# COEX_PDB_schematics.net
KiCad netlist of a schematic drawn in Altium Designer
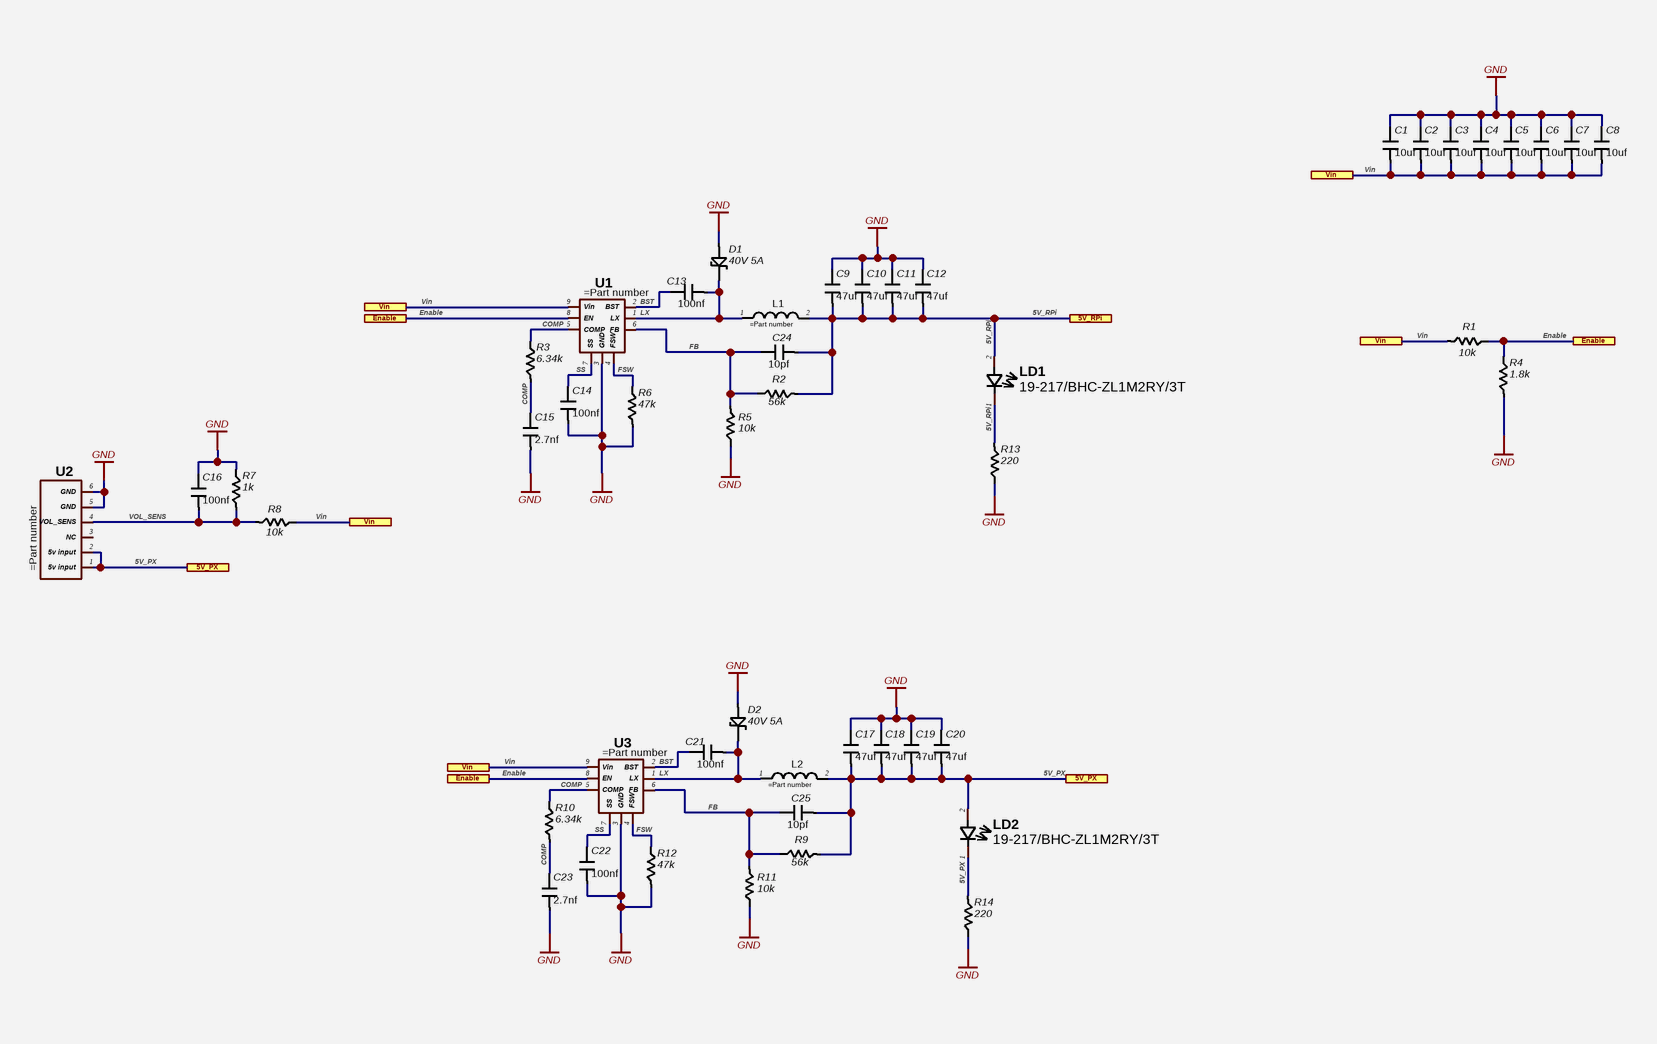
[diagram p0: COEX PDB schematics.SchDoc]

(export (version "E")
  (design (tool "Eeschema 10.0.6"))
  (components
    (comp (ref "C1")
      (value "10uf")
      (footprint "Capasitor 0805")
      (description "10uF ±20% 35V X5R 0805 Multilayer Ceramic Capacitor")
      (fields
        (field (name "PARTNUMBER") "GRM21BR6YA106ME43L")
        (field (name "MANUFACTURER") "Murata Electronics")
      )
      (libsource (lib "Schematic symbols library") (part "Capacitor MLCC"))
    )
    (comp (ref "C2")
      (value "10uf")
      (footprint "Capasitor 0805")
      (description "10uF ±20% 35V X5R 0805 Multilayer Ceramic Capacitor")
      (fields
        (field (name "PARTNUMBER") "GRM21BR6YA106ME43L")
        (field (name "MANUFACTURER") "Murata Electronics")
      )
      (libsource (lib "Schematic symbols library") (part "Capacitor MLCC"))
    )
    (comp (ref "C3")
      (value "10uf")
      (footprint "Capasitor 0805")
      (description "10uF ±20% 35V X5R 0805 Multilayer Ceramic Capacitor")
      (fields
        (field (name "PARTNUMBER") "GRM21BR6YA106ME43L")
        (field (name "MANUFACTURER") "Murata Electronics")
      )
      (libsource (lib "Schematic symbols library") (part "Capacitor MLCC"))
    )
    (comp (ref "C4")
      (value "10uf")
      (footprint "Capasitor 0805")
      (description "10uF ±20% 35V X5R 0805 Multilayer Ceramic Capacitor")
      (fields
        (field (name "PARTNUMBER") "GRM21BR6YA106ME43L")
        (field (name "MANUFACTURER") "Murata Electronics")
      )
      (libsource (lib "") (part "Capacitor MLCC_1"))
    )
    (comp (ref "C5")
      (value "10uf")
      (footprint "Capasitor 0805")
      (description "10uF ±20% 35V X5R 0805 Multilayer Ceramic Capacitor")
      (fields
        (field (name "PARTNUMBER") "GRM21BR6YA106ME43L")
        (field (name "MANUFACTURER") "Murata Electronics")
      )
      (libsource (lib "Schematic symbols library") (part "Capacitor MLCC"))
    )
    (comp (ref "C6")
      (value "10uf")
      (footprint "Capasitor 0805")
      (description "10uF ±20% 35V X5R 0805 Multilayer Ceramic Capacitor")
      (fields
        (field (name "PARTNUMBER") "GRM21BR6YA106ME43L")
        (field (name "MANUFACTURER") "Murata Electronics")
      )
      (libsource (lib "Schematic symbols library") (part "Capacitor MLCC"))
    )
    (comp (ref "C7")
      (value "10uf")
      (footprint "Capasitor 0805")
      (description "10uF ±20% 35V X5R 0805 Multilayer Ceramic Capacitor")
      (fields
        (field (name "PARTNUMBER") "GRM21BR6YA106ME43L")
        (field (name "MANUFACTURER") "Murata Electronics")
      )
      (libsource (lib "Schematic symbols library") (part "Capacitor MLCC"))
    )
    (comp (ref "C8")
      (value "10uf")
      (footprint "Capasitor 0805")
      (description "10uF ±20% 35V X5R 0805 Multilayer Ceramic Capacitor")
      (fields
        (field (name "PARTNUMBER") "GRM21BR6YA106ME43L")
        (field (name "MANUFACTURER") "Murata Electronics")
      )
      (libsource (lib "Schematic symbols library") (part "Capacitor MLCC"))
    )
    (comp (ref "C9")
      (value "47uf")
      (footprint "Capasitor 0805")
      (description "47uF ±20% 6.3V X5R 0805 Multilayer Ceramic Capacitor")
      (fields (field (name "PARTNUMBER") "JMK212BJ476MG-T") (field (name "MANUFACTURER") "Taiyo Yuden"))
      (libsource (lib "Schematic symbols library") (part "Capacitor MLCC"))
    )
    (comp (ref "C10")
      (value "47uf")
      (footprint "Capasitor 0805")
      (description "47uF ±20% 6.3V X5R 0805 Multilayer Ceramic Capacitor")
      (fields (field (name "PARTNUMBER") "JMK212BJ476MG-T") (field (name "MANUFACTURER") "Taiyo Yuden"))
      (libsource (lib "Schematic symbols library") (part "Capacitor MLCC"))
    )
    (comp (ref "C11")
      (value "47uf")
      (footprint "Capasitor 0805")
      (description "47uF ±20% 6.3V X5R 0805 Multilayer Ceramic Capacitor")
      (fields (field (name "PARTNUMBER") "JMK212BJ476MG-T") (field (name "MANUFACTURER") "Taiyo Yuden"))
      (libsource (lib "Schematic symbols library") (part "Capacitor MLCC"))
    )
    (comp (ref "C12")
      (value "47uf")
      (footprint "Capasitor 0805")
      (description "47uF ±20% 6.3V X5R 0805 Multilayer Ceramic Capacitor")
      (fields (field (name "PARTNUMBER") "JMK212BJ476MG-T") (field (name "MANUFACTURER") "Taiyo Yuden"))
      (libsource (lib "Schematic symbols library") (part "Capacitor MLCC"))
    )
    (comp (ref "C13")
      (value "100nf")
      (footprint "Capasitor 0402")
      (description "100nF ±10% 50V X5R 0402 Multilayer Ceramic Capacitor")
      (fields (field (name "PARTNUMBER") "CC0402KRX5R9BB104") (field (name "MANUFACTURER") "YAGEO"))
      (libsource (lib "Schematic symbols library") (part "Capacitor MLCC"))
    )
    (comp (ref "C14")
      (value "100nf")
      (footprint "Capasitor 0402")
      (description "100nF ±10% 50V X5R 0402 Multilayer Ceramic Capacitor")
      (fields (field (name "PARTNUMBER") "CC0402KRX5R9BB104") (field (name "MANUFACTURER") "YAGEO"))
      (libsource (lib "Schematic symbols library") (part "Capacitor MLCC"))
    )
    (comp (ref "C15")
      (value "2.7nf")
      (footprint "Capasitor 0402")
      (description "2.7nF ±10% 50V X7R 0402 Multilayer Ceramic Capacitor")
      (fields (field (name "PARTNUMBER") "CC0402KRX7R9BB272") (field (name "MANUFACTURER") "YAGEO"))
      (libsource (lib "Schematic symbols library") (part "Capacitor MLCC"))
    )
    (comp (ref "C16")
      (value "100nf")
      (footprint "Capasitor 0402")
      (description "100nF ±10% 50V X5R 0402 Multilayer Ceramic Capacitor")
      (fields (field (name "PARTNUMBER") "CC0402KRX5R9BB104") (field (name "MANUFACTURER") "YAGEO"))
      (libsource (lib "Schematic symbols library") (part "Capacitor MLCC"))
    )
    (comp (ref "C17")
      (value "47uf")
      (footprint "Capasitor 0805")
      (description "47uF ±20% 6.3V X5R 0805 Multilayer Ceramic Capacitor")
      (fields (field (name "PARTNUMBER") "JMK212BJ476MG-T") (field (name "MANUFACTURER") "Taiyo Yuden"))
      (libsource (lib "Schematic symbols library") (part "Capacitor MLCC"))
    )
    (comp (ref "C18")
      (value "47uf")
      (footprint "Capasitor 0805")
      (description "47uF ±20% 6.3V X5R 0805 Multilayer Ceramic Capacitor")
      (fields (field (name "PARTNUMBER") "JMK212BJ476MG-T") (field (name "MANUFACTURER") "Taiyo Yuden"))
      (libsource (lib "Schematic symbols library") (part "Capacitor MLCC"))
    )
    (comp (ref "C19")
      (value "47uf")
      (footprint "Capasitor 0805")
      (description "47uF ±20% 6.3V X5R 0805 Multilayer Ceramic Capacitor")
      (fields (field (name "PARTNUMBER") "JMK212BJ476MG-T") (field (name "MANUFACTURER") "Taiyo Yuden"))
      (libsource (lib "Schematic symbols library") (part "Capacitor MLCC"))
    )
    (comp (ref "C20")
      (value "47uf")
      (footprint "Capasitor 0805")
      (description "47uF ±20% 6.3V X5R 0805 Multilayer Ceramic Capacitor")
      (fields (field (name "PARTNUMBER") "JMK212BJ476MG-T") (field (name "MANUFACTURER") "Taiyo Yuden"))
      (libsource (lib "Schematic symbols library") (part "Capacitor MLCC"))
    )
    (comp (ref "C21")
      (value "100nf")
      (footprint "Capasitor 0402")
      (description "100nF ±10% 50V X5R 0402 Multilayer Ceramic Capacitor")
      (fields (field (name "PARTNUMBER") "CC0402KRX5R9BB104") (field (name "MANUFACTURER") "YAGEO"))
      (libsource (lib "Schematic symbols library") (part "Capacitor MLCC"))
    )
    (comp (ref "C22")
      (value "100nf")
      (footprint "Capasitor 0402")
      (description "100nF ±10% 50V X5R 0402 Multilayer Ceramic Capacitor")
      (fields (field (name "PARTNUMBER") "CC0402KRX5R9BB104") (field (name "MANUFACTURER") "YAGEO"))
      (libsource (lib "Schematic symbols library") (part "Capacitor MLCC"))
    )
    (comp (ref "C23")
      (value "2.7nf")
      (footprint "Capasitor 0402")
      (description "2.7nF ±10% 50V X7R 0402 Multilayer Ceramic Capacitor")
      (fields (field (name "PARTNUMBER") "CC0402KRX7R9BB272") (field (name "MANUFACTURER") "YAGEO"))
      (libsource (lib "Schematic symbols library") (part "Capacitor MLCC"))
    )
    (comp (ref "C24")
      (value "10pf")
      (footprint "Capasitor 0402")
      (description "10pF ±5% 50V NP0 0402 Multilayer Ceramic Capacitor")
      (fields (field (name "PARTNUMBER") "CC0402JRNPO9BN100") (field (name "MANUFACTURER") "YAGEO"))
      (libsource (lib "Schematic symbols library") (part "Capacitor MLCC"))
    )
    (comp (ref "C25")
      (value "10pf")
      (footprint "Capasitor 0402")
      (description "10pF ±5% 50V NP0 0402 Multilayer Ceramic Capacitor")
      (fields (field (name "PARTNUMBER") "CC0402JRNPO9BN100") (field (name "MANUFACTURER") "YAGEO"))
      (libsource (lib "Schematic symbols library") (part "Capacitor MLCC"))
    )
    (comp (ref "D1")
      (value "40V 5A")
      (footprint "SMAF")
      (description "40V 5A 450mV @ 5A SMAF Schottky Barrier Diode")
      (fields (field (name "PARTNUMBER") "SL54F") (field (name "MANUFACTURER") "MDD(Microdiode Electronics)"))
      (libsource (lib "Schematic symbols library") (part "Schottky barrier diode"))
    )
    (comp (ref "D2")
      (value "40V 5A")
      (footprint "SMAF")
      (description "40V 5A 450mV @ 5A SMAF Schottky Barrier Diode")
      (fields (field (name "PARTNUMBER") "SL54F") (field (name "MANUFACTURER") "MDD(Microdiode Electronics)"))
      (libsource (lib "Schematic symbols library") (part "Schottky barrier diode"))
    )
    (comp (ref "L1")
      (value "~")
      (footprint "Inductor SMD 7.1x6.6")
      (description "4.7uH ±20% 4.5A 45mΩ SMD,7.1x6.6x2.4mm Power Inductor")
      (fields (field (name "PARTNUMBER") "SLO0624H4R7MTT") (field (name "MANUFACTURER") "Sunltech Tech"))
      (libsource (lib "Schematic symbols library") (part "FB / Inductor"))
    )
    (comp (ref "L2")
      (value "~")
      (footprint "Inductor SMD 7.1x6.6")
      (description "4.7uH ±20% 4.5A 45mΩ SMD,7.1x6.6x2.4mm Power Inductor")
      (fields (field (name "PARTNUMBER") "SLO0624H4R7MTT") (field (name "MANUFACTURER") "Sunltech Tech"))
      (libsource (lib "Schematic symbols library") (part "FB / Inductor"))
    )
    (comp (ref "LD1")
      (value "19-217/BHC-ZL1M2RY/3T")
      (footprint "Led 0603")
      (description "Blue 465~475nm 0603 Light Emitting Diode")
      (fields (field (name "MANUFACTURER") "Everlight Elec"))
      (libsource (lib "Schematic symbols library") (part "LED"))
    )
    (comp (ref "LD2")
      (value "19-217/BHC-ZL1M2RY/3T")
      (footprint "Led 0603")
      (description "Blue 465~475nm 0603 Light Emitting Diode")
      (fields (field (name "MANUFACTURER") "Everlight Elec"))
      (libsource (lib "Schematic symbols library") (part "LED"))
    )
    (comp (ref "R1")
      (value "10k")
      (footprint "Resistor 0402")
      (description "Chip Resistor - Surface Mount 10KOhms ±1% 1/16W 0402")
      (fields (field (name "PARTNUMBER") "RC0402FR-0710KL") (field (name "MANUFACTURER") "YAGEO"))
      (libsource (lib "") (part "Resistor_1"))
    )
    (comp (ref "R2")
      (value "56k")
      (footprint "Resistor 0402")
      (description "Chip Resistor - Surface Mount 56KOhms ±1% 1/16W 0402")
      (fields (field (name "PARTNUMBER") "RC0402FR-0756KL") (field (name "MANUFACTURER") "YAGEO"))
      (libsource (lib "Schematic symbols library") (part "Resistor"))
    )
    (comp (ref "R3")
      (value "6.34k")
      (footprint "Resistor 0402")
      (description "6.34K ±1% 1/16W ±100ppm/°C 0402 Chip Resistor")
      (fields
        (field (name "PARTNUMBER") "0402WGF6341TCE")
        (field (name "MANUFACTURER") "UNI-ROYAL(Uniroyal Elec)")
      )
      (libsource (lib "Schematic symbols library") (part "Resistor"))
    )
    (comp (ref "R4")
      (value "1.8k")
      (footprint "Resistor 0402")
      (description "1.8K ±1% 1/16W ±100ppm/°C 0402 Chip Resistor")
      (fields (field (name "PARTNUMBER") "RTT021801FTH") (field (name "MANUFACTURER") "RALEC"))
      (libsource (lib "Schematic symbols library") (part "Resistor"))
    )
    (comp (ref "R5")
      (value "10k")
      (footprint "Resistor 0402")
      (description "Chip Resistor - Surface Mount 10KOhms ±1% 1/16W 0402")
      (fields (field (name "PARTNUMBER") "RC0402FR-0710KL") (field (name "MANUFACTURER") "YAGEO"))
      (libsource (lib "Schematic symbols library") (part "Resistor"))
    )
    (comp (ref "R6")
      (value "47k")
      (footprint "Resistor 0402")
      (description "47K ±1% 1/16W ±100ppm/°C 0402 Chip Resistor")
      (fields (field (name "PARTNUMBER") "AC0402FR-0747KL") (field (name "MANUFACTURER") "YAGEO"))
      (libsource (lib "Schematic symbols library") (part "Resistor"))
    )
    (comp (ref "R7")
      (value "1k")
      (footprint "Resistor 0402")
      (description "1K ±1% 1/16W ±100ppm/°C 0402 Chip Resistor")
      (fields
        (field (name "PARTNUMBER") "0402WGF1001TCE")
        (field (name "MANUFACTURER") "UNI-ROYAL(Uniroyal Elec)")
      )
      (libsource (lib "Schematic symbols library") (part "Resistor"))
    )
    (comp (ref "R8")
      (value "10k")
      (footprint "Resistor 0402")
      (description "Chip Resistor - Surface Mount 10KOhms ±1% 1/16W 0402")
      (fields (field (name "PARTNUMBER") "RC0402FR-0710KL") (field (name "MANUFACTURER") "YAGEO"))
      (libsource (lib "Schematic symbols library") (part "Resistor"))
    )
    (comp (ref "R9")
      (value "56k")
      (footprint "Resistor 0402")
      (description "Chip Resistor - Surface Mount 56KOhms ±1% 1/16W 0402")
      (fields (field (name "PARTNUMBER") "RC0402FR-0756KL") (field (name "MANUFACTURER") "YAGEO"))
      (libsource (lib "Schematic symbols library") (part "Resistor"))
    )
    (comp (ref "R10")
      (value "6.34k")
      (footprint "Resistor 0402")
      (description "6.34K ±1% 1/16W ±100ppm/°C 0402 Chip Resistor")
      (fields
        (field (name "PARTNUMBER") "0402WGF6341TCE")
        (field (name "MANUFACTURER") "UNI-ROYAL(Uniroyal Elec)")
      )
      (libsource (lib "Schematic symbols library") (part "Resistor"))
    )
    (comp (ref "R11")
      (value "10k")
      (footprint "Resistor 0402")
      (description "Chip Resistor - Surface Mount 10KOhms ±1% 1/16W 0402")
      (fields (field (name "PARTNUMBER") "RC0402FR-0710KL") (field (name "MANUFACTURER") "YAGEO"))
      (libsource (lib "Schematic symbols library") (part "Resistor"))
    )
    (comp (ref "R12")
      (value "47k")
      (footprint "Resistor 0402")
      (description "47K ±1% 1/16W ±100ppm/°C 0402 Chip Resistor")
      (fields (field (name "PARTNUMBER") "AC0402FR-0747KL") (field (name "MANUFACTURER") "YAGEO"))
      (libsource (lib "Schematic symbols library") (part "Resistor"))
    )
    (comp (ref "R13")
      (value "220")
      (footprint "Resistor 0402")
      (description "220 ±1% 1/16W ±200ppm/°C 0402 Chip Resistor")
      (fields
        (field (name "PARTNUMBER") "RC-02W2200FT")
        (field (name "MANUFACTURER") "FH(Guangdong Fenghua Advanced Tech)")
      )
      (libsource (lib "Schematic symbols library") (part "Resistor"))
    )
    (comp (ref "R14")
      (value "220")
      (footprint "Resistor 0402")
      (description "220 ±1% 1/16W ±200ppm/°C 0402 Chip Resistor")
      (fields
        (field (name "PARTNUMBER") "RC-02W2200FT")
        (field (name "MANUFACTURER") "FH(Guangdong Fenghua Advanced Tech)")
      )
      (libsource (lib "Schematic symbols library") (part "Resistor"))
    )
    (comp (ref "U1")
      (value "~")
      (footprint "SOIC-8 (Thermal pad)")
      (description "Step-Down Positive Adjustable 1 4A 200kHz ~ 2MHz SOP-8_EP_150mil DC-DC Converter")
      (fields (field (name "PARTNUMBER") "AOZ1284PI") (field (name "MANUFACTURER") "Alpha & Omega Semicon"))
      (libsource (lib "Schematic symbols library") (part "AOZ1284"))
    )
    (comp (ref "U2")
      (value "~")
      (footprint "JST-GH 6 PIN")
      (description "GH Header Male Pin 0.049\"(1.25mm) 6 SMD Wire To Board / Wire To Wire Connector")
      (fields
        (field (name "PARTNUMBER") "SM06B-GHS-TB(LF)(SN)")
        (field (name "MANUFACTURER") "JST Sales America")
      )
      (libsource (lib "Schematic symbols library") (part "JST-GH 6"))
    )
    (comp (ref "U3")
      (value "~")
      (footprint "SOIC-8 (Thermal pad)")
      (description "Step-Down Positive Adjustable 1 4A 200kHz ~ 2MHz SOP-8_EP_150mil DC-DC Converter")
      (fields (field (name "PARTNUMBER") "AOZ1284PI") (field (name "MANUFACTURER") "Alpha & Omega Semicon"))
      (libsource (lib "Schematic symbols library") (part "AOZ1284"))
    )
  )
  (nets
    (net (code "1") (name "/5V_PX") (class "Default")
      (node (ref "C17") (pin "2") (pinfunction "2_2") (pintype "passive"))
      (node (ref "C18") (pin "2") (pinfunction "2_2") (pintype "passive"))
      (node (ref "C19") (pin "2") (pinfunction "2_2") (pintype "passive"))
      (node (ref "C20") (pin "2") (pinfunction "2_2") (pintype "passive"))
      (node (ref "C25") (pin "2") (pinfunction "2_2") (pintype "passive"))
      (node (ref "L2") (pin "2") (pintype "power_in"))
      (node (ref "LD2") (pin "1") (pintype "power_in"))
      (node (ref "LD2") (pin "2") (pintype "power_in"))
      (node (ref "R14") (pin "2") (pinfunction "2_2") (pintype "passive"))
      (node (ref "R9") (pin "2") (pinfunction "2_2") (pintype "passive"))
      (node (ref "U2") (pin "1") (pinfunction "5v_input_1") (pintype "power_in"))
      (node (ref "U2") (pin "2") (pinfunction "5v_input_2") (pintype "power_in"))
    )
    (net (code "2") (name "/5V_RPi") (class "Default")
      (node (ref "C10") (pin "2") (pinfunction "2_2") (pintype "passive"))
      (node (ref "C11") (pin "2") (pinfunction "2_2") (pintype "passive"))
      (node (ref "C12") (pin "2") (pinfunction "2_2") (pintype "passive"))
      (node (ref "C24") (pin "2") (pinfunction "2_2") (pintype "passive"))
      (node (ref "C9") (pin "2") (pinfunction "2_2") (pintype "passive"))
      (node (ref "L1") (pin "2") (pintype "power_in"))
      (node (ref "LD1") (pin "1") (pintype "power_in"))
      (node (ref "LD1") (pin "2") (pintype "power_in"))
      (node (ref "R13") (pin "2") (pinfunction "2_2") (pintype "passive"))
      (node (ref "R2") (pin "2") (pinfunction "2_2") (pintype "passive"))
    )
    (net (code "3") (name "/BST") (class "Default")
      (node (ref "C13") (pin "1") (pinfunction "1_1") (pintype "passive"))
      (node (ref "C21") (pin "1") (pinfunction "1_1") (pintype "passive"))
      (node (ref "U1") (pin "2") (pinfunction "BST_2") (pintype "power_in"))
      (node (ref "U3") (pin "2") (pinfunction "BST_2") (pintype "power_in"))
    )
    (net (code "4") (name "/COMP") (class "Default")
      (node (ref "C15") (pin "1") (pinfunction "1_1") (pintype "passive"))
      (node (ref "C23") (pin "1") (pinfunction "1_1") (pintype "passive"))
      (node (ref "R10") (pin "1") (pinfunction "1_1") (pintype "passive"))
      (node (ref "R10") (pin "2") (pinfunction "2_2") (pintype "passive"))
      (node (ref "R3") (pin "1") (pinfunction "1_1") (pintype "passive"))
      (node (ref "R3") (pin "2") (pinfunction "2_2") (pintype "passive"))
      (node (ref "U1") (pin "5") (pinfunction "COMP_5") (pintype "power_in"))
      (node (ref "U3") (pin "5") (pinfunction "COMP_5") (pintype "power_in"))
    )
    (net (code "5") (name "/Enable") (class "Default")
      (node (ref "R1") (pin "1") (pinfunction "1_1") (pintype "passive"))
      (node (ref "R4") (pin "1") (pinfunction "1_1") (pintype "passive"))
      (node (ref "U1") (pin "8") (pinfunction "EN_8") (pintype "power_in"))
      (node (ref "U3") (pin "8") (pinfunction "EN_8") (pintype "power_in"))
    )
    (net (code "6") (name "/FB") (class "Default")
      (node (ref "C24") (pin "1") (pinfunction "1_1") (pintype "passive"))
      (node (ref "C25") (pin "1") (pinfunction "1_1") (pintype "passive"))
      (node (ref "R11") (pin "2") (pinfunction "2_2") (pintype "passive"))
      (node (ref "R2") (pin "1") (pinfunction "1_1") (pintype "passive"))
      (node (ref "R5") (pin "2") (pinfunction "2_2") (pintype "passive"))
      (node (ref "R9") (pin "1") (pinfunction "1_1") (pintype "passive"))
      (node (ref "U1") (pin "6") (pinfunction "FB_6") (pintype "power_in"))
      (node (ref "U3") (pin "6") (pinfunction "FB_6") (pintype "power_in"))
    )
    (net (code "7") (name "/FSW") (class "Default")
      (node (ref "R12") (pin "1") (pinfunction "1_1") (pintype "passive"))
      (node (ref "R6") (pin "1") (pinfunction "1_1") (pintype "passive"))
      (node (ref "U1") (pin "4") (pinfunction "FSW_4") (pintype "power_in"))
      (node (ref "U3") (pin "4") (pinfunction "FSW_4") (pintype "power_in"))
    )
    (net (code "8") (name "/LX") (class "Default")
      (node (ref "C13") (pin "2") (pinfunction "2_2") (pintype "passive"))
      (node (ref "C21") (pin "2") (pinfunction "2_2") (pintype "passive"))
      (node (ref "D1") (pin "1") (pinfunction "1_1") (pintype "passive"))
      (node (ref "D2") (pin "1") (pinfunction "1_1") (pintype "passive"))
      (node (ref "L1") (pin "1") (pintype "power_in"))
      (node (ref "L2") (pin "1") (pintype "power_in"))
      (node (ref "U1") (pin "1") (pinfunction "LX_1") (pintype "power_in"))
      (node (ref "U3") (pin "1") (pinfunction "LX_1") (pintype "power_in"))
    )
    (net (code "9") (name "/SS") (class "Default")
      (node (ref "C14") (pin "1") (pinfunction "1_1") (pintype "passive"))
      (node (ref "C22") (pin "1") (pinfunction "1_1") (pintype "passive"))
      (node (ref "U1") (pin "7") (pinfunction "SS_7") (pintype "power_in"))
      (node (ref "U3") (pin "7") (pinfunction "SS_7") (pintype "power_in"))
    )
    (net (code "10") (name "/VOL_SENS") (class "Default")
      (node (ref "C16") (pin "2") (pinfunction "2_2") (pintype "passive"))
      (node (ref "R7") (pin "2") (pinfunction "2_2") (pintype "passive"))
      (node (ref "R8") (pin "2") (pinfunction "2_2") (pintype "passive"))
      (node (ref "U2") (pin "4") (pinfunction "VOL_SENS_4") (pintype "power_in"))
    )
    (net (code "11") (name "/Vin") (class "Default")
      (node (ref "C1") (pin "2") (pinfunction "2_2") (pintype "passive"))
      (node (ref "C2") (pin "2") (pinfunction "2_2") (pintype "passive"))
      (node (ref "C3") (pin "2") (pinfunction "2_2") (pintype "passive"))
      (node (ref "C4") (pin "2") (pinfunction "2_2") (pintype "passive"))
      (node (ref "C5") (pin "2") (pinfunction "2_2") (pintype "passive"))
      (node (ref "C6") (pin "2") (pinfunction "2_2") (pintype "passive"))
      (node (ref "C7") (pin "2") (pinfunction "2_2") (pintype "passive"))
      (node (ref "C8") (pin "2") (pinfunction "2_2") (pintype "passive"))
      (node (ref "R1") (pin "2") (pinfunction "2_2") (pintype "passive"))
      (node (ref "R8") (pin "1") (pinfunction "1_1") (pintype "passive"))
      (node (ref "U1") (pin "9") (pinfunction "Vin_9") (pintype "power_in"))
      (node (ref "U3") (pin "9") (pinfunction "Vin_9") (pintype "power_in"))
    )
    (net (code "12") (name "GND") (class "Default")
      (node (ref "C1") (pin "1") (pinfunction "1_1") (pintype "passive"))
      (node (ref "C10") (pin "1") (pinfunction "1_1") (pintype "passive"))
      (node (ref "C11") (pin "1") (pinfunction "1_1") (pintype "passive"))
      (node (ref "C12") (pin "1") (pinfunction "1_1") (pintype "passive"))
      (node (ref "C14") (pin "2") (pinfunction "2_2") (pintype "passive"))
      (node (ref "C15") (pin "2") (pinfunction "2_2") (pintype "passive"))
      (node (ref "C16") (pin "1") (pinfunction "1_1") (pintype "passive"))
      (node (ref "C17") (pin "1") (pinfunction "1_1") (pintype "passive"))
      (node (ref "C18") (pin "1") (pinfunction "1_1") (pintype "passive"))
      (node (ref "C19") (pin "1") (pinfunction "1_1") (pintype "passive"))
      (node (ref "C2") (pin "1") (pinfunction "1_1") (pintype "passive"))
      (node (ref "C20") (pin "1") (pinfunction "1_1") (pintype "passive"))
      (node (ref "C22") (pin "2") (pinfunction "2_2") (pintype "passive"))
      (node (ref "C23") (pin "2") (pinfunction "2_2") (pintype "passive"))
      (node (ref "C3") (pin "1") (pinfunction "1_1") (pintype "passive"))
      (node (ref "C4") (pin "1") (pinfunction "1_1") (pintype "passive"))
      (node (ref "C5") (pin "1") (pinfunction "1_1") (pintype "passive"))
      (node (ref "C6") (pin "1") (pinfunction "1_1") (pintype "passive"))
      (node (ref "C7") (pin "1") (pinfunction "1_1") (pintype "passive"))
      (node (ref "C8") (pin "1") (pinfunction "1_1") (pintype "passive"))
      (node (ref "C9") (pin "1") (pinfunction "1_1") (pintype "passive"))
      (node (ref "D1") (pin "2") (pinfunction "2_2") (pintype "passive"))
      (node (ref "D2") (pin "2") (pinfunction "2_2") (pintype "passive"))
      (node (ref "R11") (pin "1") (pinfunction "1_1") (pintype "passive"))
      (node (ref "R12") (pin "2") (pinfunction "2_2") (pintype "passive"))
      (node (ref "R13") (pin "1") (pinfunction "1_1") (pintype "passive"))
      (node (ref "R14") (pin "1") (pinfunction "1_1") (pintype "passive"))
      (node (ref "R4") (pin "2") (pinfunction "2_2") (pintype "passive"))
      (node (ref "R5") (pin "1") (pinfunction "1_1") (pintype "passive"))
      (node (ref "R6") (pin "2") (pinfunction "2_2") (pintype "passive"))
      (node (ref "R7") (pin "1") (pinfunction "1_1") (pintype "passive"))
      (node (ref "U1") (pin "3") (pinfunction "GND_3") (pintype "power_in"))
      (node (ref "U2") (pin "5") (pinfunction "GND_5") (pintype "power_in"))
      (node (ref "U2") (pin "6") (pinfunction "GND_6") (pintype "power_in"))
      (node (ref "U3") (pin "3") (pinfunction "GND_3") (pintype "power_in"))
    )
    (net (code "13") (name "unconnected-(U2-NC-Pad3)") (class "Default")
      (node (ref "U2") (pin "3") (pinfunction "NC_3") (pintype "power_in"))
    )
  )
)
